# RNG_SATA.net
KiCad netlist of a schematic drawn in Altium Designer
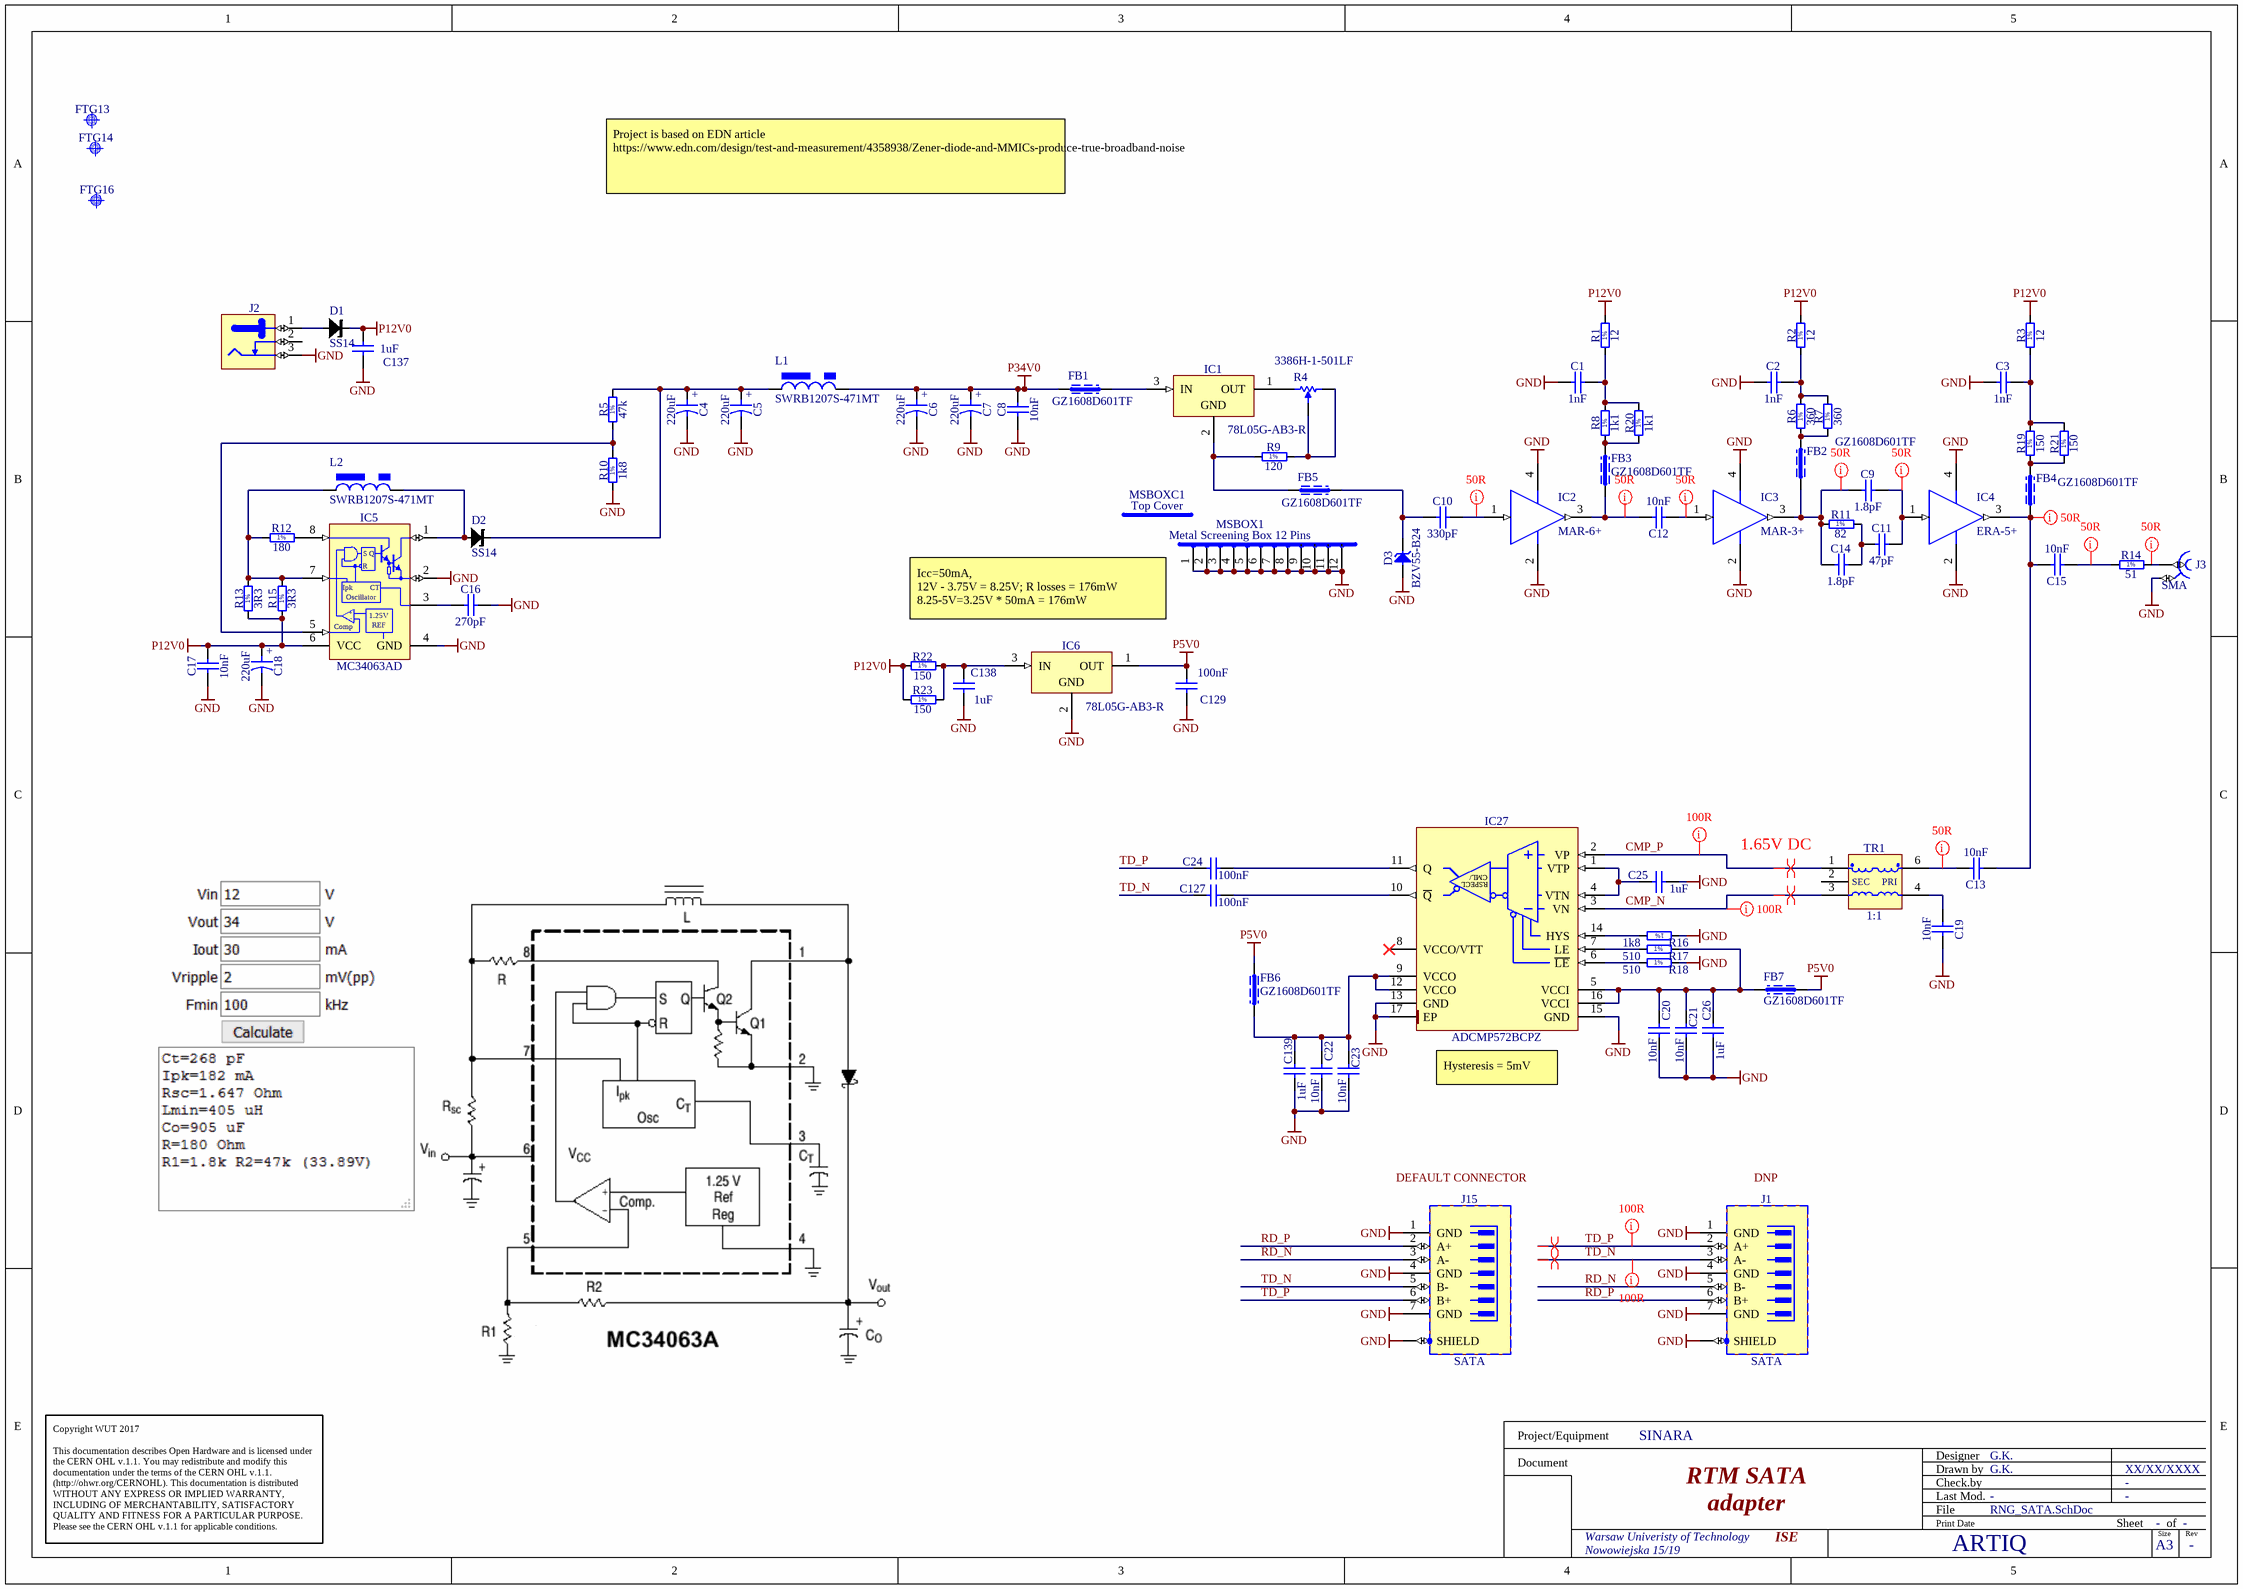
[diagram p0: RNG_SATA.SchDoc]

(export (version "E")
  (design (tool "Eeschema 10.0.6"))
  (components
    (comp (ref "C1")
      (value "1nF")
      (footprint "CAPC1608X90N")
      (description "Non-polarised capacitor")
      (fields
        (field (name "PART NUMBER") "CC0603_1NF_50V_1%_NP0")
        (field (name "VOLTAGE") "50V")
        (field (name "AUTHOR") "CERN DEM JLC")
      )
      (libsource (lib "Capacitors") (part "Capacitor - non polarized"))
    )
    (comp (ref "C2")
      (value "1nF")
      (footprint "CAPC1608X90N")
      (description "Non-polarised capacitor")
      (fields
        (field (name "PART NUMBER") "CC0603_1NF_50V_1%_NP0")
        (field (name "VOLTAGE") "50V")
        (field (name "AUTHOR") "CERN DEM JLC")
      )
      (libsource (lib "Capacitors") (part "Capacitor - non polarized"))
    )
    (comp (ref "C3")
      (value "1nF")
      (footprint "CAPC1608X90N")
      (description "Non-polarised capacitor")
      (fields
        (field (name "PART NUMBER") "CC0603_1NF_50V_1%_NP0")
        (field (name "VOLTAGE") "50V")
        (field (name "AUTHOR") "CERN DEM JLC")
      )
      (libsource (lib "Capacitors") (part "Capacitor - non polarized"))
    )
    (comp (ref "C4")
      (value "220uF")
      (footprint "CAPAE830X1020N")
      (description "Polarised capacitor")
      (fields
        (field (name "PART NUMBER") "CAE830-1020_220UF_35V_20%")
        (field (name "VOLTAGE") "35V")
        (field (name "AUTHOR") "CERN DEM JLC")
      )
      (libsource (lib "Capacitors") (part "Capacitor - polarized"))
    )
    (comp (ref "C5")
      (value "220uF")
      (footprint "CAPAE830X1020N")
      (description "Polarised capacitor")
      (fields
        (field (name "PART NUMBER") "CAE830-1020_220UF_35V_20%")
        (field (name "VOLTAGE") "35V")
        (field (name "AUTHOR") "CERN DEM JLC")
      )
      (libsource (lib "Capacitors") (part "Capacitor - polarized"))
    )
    (comp (ref "C6")
      (value "220uF")
      (footprint "CAPAE830X1020N")
      (description "Polarised capacitor")
      (fields
        (field (name "PART NUMBER") "CAE830-1020_220UF_35V_20%")
        (field (name "VOLTAGE") "35V")
        (field (name "AUTHOR") "CERN DEM JLC")
      )
      (libsource (lib "Capacitors") (part "Capacitor - polarized"))
    )
    (comp (ref "C7")
      (value "220uF")
      (footprint "CAPAE830X1020N")
      (description "Polarised capacitor")
      (fields
        (field (name "PART NUMBER") "CAE830-1020_220UF_35V_20%")
        (field (name "VOLTAGE") "35V")
        (field (name "AUTHOR") "CERN DEM JLC")
      )
      (libsource (lib "Capacitors") (part "Capacitor - polarized"))
    )
    (comp (ref "C8")
      (value "10nF")
      (footprint "CAPC1608X87N")
      (description "Non-polarised capacitor")
      (fields
        (field (name "PART NUMBER") "CC0603_10NF_50V_5%_C0G")
        (field (name "VOLTAGE") "50V")
        (field (name "AUTHOR") "CERN DEM JLC")
      )
      (libsource (lib "Capacitors") (part "Capacitor - non polarized"))
    )
    (comp (ref "C9")
      (value "1.8pF")
      (footprint "CAPC1608X87N")
      (description "Non-polarised capacitor")
      (fields
        (field (name "PART NUMBER") "CC0603_1.8PF_50V_0.25PF_NP0")
        (field (name "VOLTAGE") "50V")
        (field (name "AUTHOR") "CERN DEM JLC")
      )
      (libsource (lib "Capacitors") (part "Capacitor - non polarized"))
    )
    (comp (ref "C10")
      (value "330pF")
      (footprint "CAPC1608X87N")
      (description "Non-polarised capacitor")
      (fields
        (field (name "PART NUMBER") "CC0603_330PF_50V_5%_NP0")
        (field (name "VOLTAGE") "50V")
        (field (name "AUTHOR") "CERN DEM JLC")
      )
      (libsource (lib "Capacitors") (part "Capacitor - non polarized"))
    )
    (comp (ref "C11")
      (value "47pF")
      (footprint "CAPC1608X87N")
      (description "Non-polarised capacitor")
      (fields
        (field (name "PART NUMBER") "CC0603_47PF_50V_5%_NP0")
        (field (name "VOLTAGE") "50V")
        (field (name "AUTHOR") "CERN DEM JLC")
      )
      (libsource (lib "Capacitors") (part "Capacitor - non polarized"))
    )
    (comp (ref "C12")
      (value "10nF")
      (footprint "CAPC1608X87N")
      (description "Non-polarised capacitor")
      (fields
        (field (name "PART NUMBER") "CC0603_10NF_50V_5%_C0G")
        (field (name "VOLTAGE") "50V")
        (field (name "AUTHOR") "CERN DEM JLC")
      )
      (libsource (lib "Capacitors") (part "Capacitor - non polarized"))
    )
    (comp (ref "C13")
      (value "10nF")
      (footprint "CAPC1608X87N")
      (description "Non-polarised capacitor")
      (fields
        (field (name "PART NUMBER") "CC0603_10NF_50V_5%_C0G")
        (field (name "VOLTAGE") "50V")
        (field (name "AUTHOR") "CERN DEM JLC")
      )
      (libsource (lib "Capacitors") (part "Capacitor - non polarized"))
    )
    (comp (ref "C14")
      (value "1.8pF")
      (footprint "CAPC1608X87N")
      (description "Non-polarised capacitor")
      (fields
        (field (name "PART NUMBER") "CC0603_1.8PF_50V_0.25PF_NP0")
        (field (name "VOLTAGE") "50V")
        (field (name "AUTHOR") "CERN DEM JLC")
      )
      (libsource (lib "Capacitors") (part "Capacitor - non polarized"))
    )
    (comp (ref "C15")
      (value "10nF")
      (footprint "CAPC1608X87N")
      (description "Non-polarised capacitor")
      (fields
        (field (name "PART NUMBER") "CC0603_10NF_50V_5%_C0G")
        (field (name "VOLTAGE") "50V")
        (field (name "AUTHOR") "CERN DEM JLC")
      )
      (libsource (lib "Capacitors") (part "Capacitor - non polarized"))
    )
    (comp (ref "C16")
      (value "270pF")
      (footprint "CAPC1608X87N")
      (description "Non-polarised capacitor")
      (fields
        (field (name "PART NUMBER") "CC0603_270PF_50V_5%_NP0")
        (field (name "VOLTAGE") "50V")
        (field (name "AUTHOR") "CERN DEM JLC")
      )
      (libsource (lib "Capacitors") (part "Capacitor - non polarized"))
    )
    (comp (ref "C17")
      (value "10nF")
      (footprint "CAPC1608X87N")
      (description "Non-polarised capacitor")
      (fields
        (field (name "PART NUMBER") "CC0603_10NF_50V_5%_C0G")
        (field (name "VOLTAGE") "50V")
        (field (name "AUTHOR") "CERN DEM JLC")
      )
      (libsource (lib "Capacitors") (part "Capacitor - non polarized"))
    )
    (comp (ref "C18")
      (value "220uF")
      (footprint "CAPAE830X1020N")
      (description "Polarised capacitor")
      (fields
        (field (name "PART NUMBER") "CAE830-1020_220UF_35V_20%")
        (field (name "VOLTAGE") "35V")
        (field (name "AUTHOR") "CERN DEM JLC")
      )
      (libsource (lib "Capacitors") (part "Capacitor - polarized"))
    )
    (comp (ref "C19")
      (value "10nF")
      (footprint "CAPC1608X87N")
      (description "Non-polarised capacitor")
      (fields
        (field (name "PART NUMBER") "CC0603_10NF_50V_5%_C0G")
        (field (name "VOLTAGE") "50V")
        (field (name "AUTHOR") "CERN DEM JLC")
      )
      (libsource (lib "Capacitors") (part "Capacitor - non polarized"))
    )
    (comp (ref "C20")
      (value "10nF")
      (footprint "CAPC1608X87N")
      (description "Non-polarised capacitor")
      (fields
        (field (name "PART NUMBER") "CC0603_10NF_50V_5%_C0G")
        (field (name "VOLTAGE") "50V")
        (field (name "AUTHOR") "CERN DEM JLC")
      )
      (libsource (lib "Capacitors") (part "Capacitor - non polarized"))
    )
    (comp (ref "C21")
      (value "10nF")
      (footprint "CAPC1608X87N")
      (description "Non-polarised capacitor")
      (fields
        (field (name "PART NUMBER") "CC0603_10NF_50V_5%_C0G")
        (field (name "VOLTAGE") "50V")
        (field (name "AUTHOR") "CERN DEM JLC")
      )
      (libsource (lib "Capacitors") (part "Capacitor - non polarized"))
    )
    (comp (ref "C22")
      (value "10nF")
      (footprint "CAPC1608X87N")
      (description "Non-polarised capacitor")
      (fields
        (field (name "PART NUMBER") "CC0603_10NF_50V_5%_C0G")
        (field (name "VOLTAGE") "50V")
        (field (name "AUTHOR") "CERN DEM JLC")
      )
      (libsource (lib "Capacitors") (part "Capacitor - non polarized"))
    )
    (comp (ref "C23")
      (value "10nF")
      (footprint "CAPC1608X87N")
      (description "Non-polarised capacitor")
      (fields
        (field (name "PART NUMBER") "CC0603_10NF_50V_5%_C0G")
        (field (name "VOLTAGE") "50V")
        (field (name "AUTHOR") "CERN DEM JLC")
      )
      (libsource (lib "Capacitors") (part "Capacitor - non polarized"))
    )
    (comp (ref "C24")
      (value "100nF")
      (footprint "CAPC1005X55N")
      (description "Non-polarised capacitor")
      (fields
        (field (name "PART NUMBER") "CC0402_100NF_16V_10%_X7R")
        (field (name "VOLTAGE") "16V")
        (field (name "AUTHOR") "CERN DEM JLC")
      )
      (libsource (lib "Capacitors") (part "Capacitor - non polarized"))
    )
    (comp (ref "C25")
      (value "1uF")
      (footprint "CAPC1608X87N")
      (description "Non-polarised capacitor")
      (fields
        (field (name "PART NUMBER") "CC0603_1UF_16V_10%_X7R")
        (field (name "VOLTAGE") "16V")
        (field (name "AUTHOR") "CERN DEM JLC")
      )
      (libsource (lib "Capacitors") (part "Capacitor - non polarized"))
    )
    (comp (ref "C26")
      (value "1uF")
      (footprint "CAPC1608X87N")
      (description "Non-polarised capacitor")
      (fields
        (field (name "PART NUMBER") "CC0603_1UF_16V_10%_X7R")
        (field (name "VOLTAGE") "16V")
        (field (name "AUTHOR") "CERN DEM JLC")
      )
      (libsource (lib "Capacitors") (part "Capacitor - non polarized"))
    )
    (comp (ref "C127")
      (value "100nF")
      (footprint "CAPC1005X55N")
      (description "Non-polarised capacitor")
      (fields
        (field (name "PART NUMBER") "CC0402_100NF_16V_10%_X7R")
        (field (name "VOLTAGE") "16V")
        (field (name "AUTHOR") "CERN DEM JLC")
      )
      (libsource (lib "Capacitors") (part "Capacitor - non polarized"))
    )
    (comp (ref "C129")
      (value "100nF")
      (footprint "CAPC1005X55N")
      (description "Non-polarised capacitor")
      (fields
        (field (name "PART NUMBER") "CC0402_100NF_16V_10%_X7R")
        (field (name "VOLTAGE") "16V")
        (field (name "AUTHOR") "CERN DEM JLC")
      )
      (libsource (lib "Capacitors") (part "Capacitor - non polarized"))
    )
    (comp (ref "C137")
      (value "1uF")
      (footprint "CAPC1608X87N")
      (description "Non-polarised capacitor")
      (fields
        (field (name "PART NUMBER") "CC0603_1UF_16V_10%_X7R")
        (field (name "VOLTAGE") "16V")
        (field (name "AUTHOR") "CERN DEM JLC")
      )
      (libsource (lib "Capacitors") (part "Capacitor - non polarized"))
    )
    (comp (ref "C138")
      (value "1uF")
      (footprint "CAPC1608X87N")
      (description "Non-polarised capacitor")
      (fields
        (field (name "PART NUMBER") "CC0603_1UF_16V_10%_X7R")
        (field (name "VOLTAGE") "16V")
        (field (name "AUTHOR") "CERN DEM JLC")
      )
      (libsource (lib "Capacitors") (part "Capacitor - non polarized"))
    )
    (comp (ref "C139")
      (value "1uF")
      (footprint "CAPC1608X87N")
      (description "Non-polarised capacitor")
      (fields
        (field (name "PART NUMBER") "CC0603_1UF_16V_10%_X7R")
        (field (name "VOLTAGE") "16V")
        (field (name "AUTHOR") "CERN DEM JLC")
      )
      (libsource (lib "Capacitors") (part "Capacitor - non polarized"))
    )
    (comp (ref "D1")
      (value "SS14")
      (footprint "DO-214AC/SMA")
      (description "1A 80V shottky diode (Maritex)")
      (libsource (lib "Diodes") (part "D_SS14"))
    )
    (comp (ref "D2")
      (value "SS14")
      (footprint "DO-214AC/SMA")
      (description "1A 80V shottky diode (Maritex)")
      (libsource (lib "Diodes") (part "D_SS14"))
    )
    (comp (ref "D3")
      (value "BZV55-B24")
      (footprint "DIOMELF3515N")
      (description "Zener Diode")
      (fields
        (field (name "VOLTAGE") "24V")
        (field (name "POWER") "500mW")
        (field (name "AUTHOR") "CERN DEM JLC")
      )
      (libsource (lib "ICs And Semiconductors") (part "Diode Zener"))
    )
    (comp (ref "FB1")
      (value "GZ1608D601TF")
      (footprint "0603L")
      (description "ferrite bead 100R@100MHz 1A")
      (libsource (lib "Inductors_Transformers") (part "L_FERRITE_BEAD_0603"))
    )
    (comp (ref "FB2")
      (value "GZ1608D601TF")
      (footprint "0603L")
      (description "ferrite bead 100R@100MHz 1A")
      (libsource (lib "Inductors_Transformers") (part "L_FERRITE_BEAD_0603"))
    )
    (comp (ref "FB3")
      (value "GZ1608D601TF")
      (footprint "0603L")
      (description "ferrite bead 100R@100MHz 1A")
      (libsource (lib "Inductors_Transformers") (part "L_FERRITE_BEAD_0603"))
    )
    (comp (ref "FB4")
      (value "GZ1608D601TF")
      (footprint "0603L")
      (description "ferrite bead 100R@100MHz 1A")
      (libsource (lib "Inductors_Transformers") (part "L_FERRITE_BEAD_0603"))
    )
    (comp (ref "FB5")
      (value "GZ1608D601TF")
      (footprint "0603L")
      (description "ferrite bead 100R@100MHz 1A")
      (libsource (lib "Inductors_Transformers") (part "L_FERRITE_BEAD_0603"))
    )
    (comp (ref "FB6")
      (value "GZ1608D601TF")
      (footprint "0603L")
      (description "ferrite bead 100R@100MHz 1A")
      (libsource (lib "Inductors_Transformers") (part "L_FERRITE_BEAD_0603"))
    )
    (comp (ref "FB7")
      (value "GZ1608D601TF")
      (footprint "0603L")
      (description "ferrite bead 100R@100MHz 1A")
      (libsource (lib "Inductors_Transformers") (part "L_FERRITE_BEAD_0603"))
    )
    (comp (ref "FTG13")
      (value "Use only in PCB")
      (footprint "FIDUCIAL_TOP_C100-200")
      (description "Fiducial Target")
      (fields (field (name "PART NUMBER") "FIDUCIAL_TARGET_C100-200") (field (name "AUTHOR") "CERN DEM JLC"))
      (libsource (lib "Eletro-mechanical") (part "Fiducial Target"))
    )
    (comp (ref "FTG14")
      (value "Use only in PCB")
      (footprint "FIDUCIAL_TOP_S100-200")
      (description "Fiducial Target")
      (fields (field (name "PART NUMBER") "FIDUCIAL_TARGET_S100-200") (field (name "AUTHOR") "CERN DEM JLC"))
      (libsource (lib "Eletro-mechanical") (part "Fiducial Target"))
    )
    (comp (ref "FTG16")
      (value "Use only in PCB")
      (footprint "FIDUCIAL_TOP_S100-200")
      (description "Fiducial Target")
      (fields (field (name "PART NUMBER") "FIDUCIAL_TARGET_S100-200") (field (name "AUTHOR") "CERN DEM JLC"))
      (libsource (lib "Eletro-mechanical") (part "Fiducial Target"))
    )
    (comp (ref "IC1")
      (value "78L05G-AB3-R")
      (footprint "SOT89")
      (description "3-Terminal Regulator 1=OUT 2=GND 3=IN")
      (fields
        (field (name "PART NUMBER") "L78L05ACUTR")
        (field (name "MANUFACTURER") "ST MICROELECTRONICS")
        (field (name "AUTHOR") "CERN DEM JLC")
      )
      (libsource (lib "ICs And Semiconductors") (part "REG3 1OUT-2GND-3IN"))
    )
    (comp (ref "IC2")
      (value "MAR-6+")
      (footprint "MINI-CIRCUITS_VV105")
      (description "Monolithic Amplifier DC-2GHz")
      (fields (field (name "MANUFACTURER") "MINI-CIRCUITS") (field (name "AUTHOR") "CERN DEM MR"))
      (libsource (lib "ICs_Analog_Interfaces") (part "RF_MAR-6+"))
    )
    (comp (ref "IC3")
      (value "MAR-3+")
      (footprint "MINI-CIRCUITS_VV105")
      (description "Monolithic Amplifier DC-2GHz")
      (fields (field (name "MANUFACTURER") "MINI-CIRCUITS") (field (name "AUTHOR") "CERN DEM MR"))
      (libsource (lib "ICs_Analog_Interfaces") (part "RF_MAR-3+"))
    )
    (comp (ref "IC4")
      (value "ERA-5+")
      (footprint "MINI-CIRCUITS_VV105")
      (description "Monolithic Amplifier DC-4GHz")
      (fields (field (name "MANUFACTURER") "MINI-CIRCUITS") (field (name "AUTHOR") "CERN DEM MR"))
      (libsource (lib "ICs_Analog_Interfaces") (part "RF_ERA-5+"))
    )
    (comp (ref "IC5")
      (value "MC34063AD")
      (footprint "SOIC127P600X175-8N")
      (description "3V to 40V 1.5A Peak Boost/Buck/Inverting Switching Regulator")
      (fields (field (name "MANUFACTURER") "TEXAS INSTRUMENTS") (field (name "AUTHOR") "CERN DEM JLC"))
      (libsource (lib "ICs And Semiconductors") (part "MC34063A"))
    )
    (comp (ref "IC6")
      (value "78L05G-AB3-R")
      (footprint "SOT89")
      (description "3-Terminal Regulator 1=OUT 2=GND 3=IN")
      (fields
        (field (name "PART NUMBER") "L78L05ACUTR")
        (field (name "MANUFACTURER") "ST MICROELECTRONICS")
        (field (name "AUTHOR") "CERN DEM JLC")
      )
      (libsource (lib "ICs And Semiconductors") (part "REG3 1OUT-2GND-3IN"))
    )
    (comp (ref "IC27")
      (value "ADCMP572BCPZ")
      (footprint "QFN50P300X300X100-17N-S145")
      (description "Ultrafast 3.3V/5V Single-Supply SiGe Comparator")
      (fields (field (name "MANUFACTURER") "ANALOG DEVICES") (field (name "AUTHOR") "CERN DEM JLC"))
      (libsource (lib "ICs And Semiconductors") (part "ADCMP573BCPZ"))
    )
    (comp (ref "J1")
      (value "SATA")
      (footprint "3M_5607-4200-SH")
      (description "7 Pin + 1 Shield SATA Receptacle")
      (fields
        (field (name "PART NUMBER") "3M_5607-4200-SH")
        (field (name "MANUFACTURER") "3M")
        (field (name "AUTHOR") "CERN DEM JLC")
      )
      (libsource (lib "Connectors") (part "Connector SATA 7 Male + 1 Shield"))
    )
    (comp (ref "J2")
      (value "Jack")
      (footprint "CLIFF_FC68148(DC-10A)")
      (description "12V /  5A, 2.1mm Diameter Pin, DC Power Socket With  Switch. DC10A Type")
      (fields
        (field (name "PART NUMBER") "CLIFF_FC68148(DC-10A)")
        (field (name "MANUFACTURER") "CLIFF ELECTRONIC COMPONENTS")
        (field (name "AUTHOR") "CERN DEM JLC")
      )
      (libsource (lib "Connectors") (part "CLIFF_FC68148(DC-10A)"))
    )
    (comp (ref "J3")
      (value "SMA")
      (footprint "RF249BT0050GHDW")
      (description "50 Ohm Through Hole SMA Right Angle PCB Jack")
      (fields
        (field (name "PART NUMBER") "AdamTech_RF249BT0050GHDW")
        (field (name "MANUFACTURER") "AdamTech")
        (field (name "AUTHOR") "GK")
      )
      (libsource (lib "Connectors") (part "CON_SMA_RF249BT0050GHDW"))
    )
    (comp (ref "J15")
      (value "SATA")
      (footprint "3M_5607-4200-SH")
      (description "7 Pin + 1 Shield SATA Receptacle")
      (fields
        (field (name "PART NUMBER") "3M_5607-4200-SH")
        (field (name "MANUFACTURER") "3M")
        (field (name "AUTHOR") "CERN DEM JLC")
      )
      (libsource (lib "Connectors") (part "Connector SATA 7 Male + 1 Shield"))
    )
    (comp (ref "L1")
      (value "SWRB1207S-471MT")
      (footprint "choke_DLCSS124")
      (description "inductor")
      (libsource (lib "Inductors_Transformers") (part "L_POWER_CSS124"))
    )
    (comp (ref "L2")
      (value "SWRB1207S-471MT")
      (footprint "choke_DLCSS124")
      (description "inductor")
      (libsource (lib "Inductors_Transformers") (part "L_POWER_CSS124"))
    )
    (comp (ref "MSBOX1")
      (value "Metal Screening Box 12 Pins")
      (footprint "MSBOX_TE_2118728-2")
      (fields
        (field (name "PART NUMBER") "MSBOX_TE_2118728-2")
        (field (name "MANUFACTURER") "Tyco Electronics")
        (field (name "MANUFACTURER PART NUMBER") "BMI-S-202-F")
        (field (name "AUTHOR") "GK")
      )
      (libsource (lib "Mechanical") (part "SH_TE_2118728-2"))
    )
    (comp (ref "MSBOXC1")
      (value "Top Cover")
      (footprint "MSBOX_TE_2118727-2")
      (description "Metal Screening Box - Top Cover 0 Pin")
      (fields
        (field (name "PART NUMBER") "MSBOX_TE_2118727-2")
        (field (name "MANUFACTURER") "Tyco Electronics")
        (field (name "AUTHOR") "GK")
      )
      (libsource (lib "Mechanical") (part "SH_TE_2118727-2"))
    )
    (comp (ref "R1")
      (value "12")
      (footprint "RESC1608X55N")
      (description "Resistor - 1%")
      (fields
        (field (name "PART NUMBER") "R0603_12R_1%_0.1W_100PPM")
        (field (name "POWER") "0.1W")
        (field (name "AUTHOR") "CERN DEM JLC")
      )
      (libsource (lib "Resistors") (part "Resistor - 1%"))
    )
    (comp (ref "R2")
      (value "12")
      (footprint "RESC1608X55N")
      (description "Resistor - 1%")
      (fields
        (field (name "PART NUMBER") "R0603_12R_1%_0.1W_100PPM")
        (field (name "POWER") "0.1W")
        (field (name "AUTHOR") "CERN DEM JLC")
      )
      (libsource (lib "Resistors") (part "Resistor - 1%"))
    )
    (comp (ref "R3")
      (value "12")
      (footprint "RESC1608X55N")
      (description "Resistor - 1%")
      (fields
        (field (name "PART NUMBER") "R0603_12R_1%_0.1W_100PPM")
        (field (name "POWER") "0.1W")
        (field (name "AUTHOR") "CERN DEM JLC")
      )
      (libsource (lib "Resistors") (part "Resistor - 1%"))
    )
    (comp (ref "R4")
      (value "3386H-1-501LF")
      (footprint "BOUR-3386H")
      (fields (field (name "TOLERANCE") "10%") (field (name "MANUFACTURER") "Bourns"))
      (libsource (lib "Altium Content Vault") (part "RES-ADJ-3_A"))
    )
    (comp (ref "R5")
      (value "47k")
      (footprint "RESC1608X55N")
      (description "Resistor - 1%")
      (fields
        (field (name "PART NUMBER") "R0603_47K_1%_0.1W_100PPM")
        (field (name "POWER") "0.1W")
        (field (name "AUTHOR") "CERN DEM JLC")
      )
      (libsource (lib "Resistors") (part "Resistor - 1%"))
    )
    (comp (ref "R6")
      (value "360")
      (footprint "RESC2012X60N")
      (description "Resistor - 1%")
      (fields
        (field (name "PART NUMBER") "R0805_360R_1%_0.125W_100PPM")
        (field (name "POWER") "0.125W")
        (field (name "AUTHOR") "CERN DEM JLC")
      )
      (libsource (lib "Resistors") (part "Resistor - 1%"))
    )
    (comp (ref "R7")
      (value "360")
      (footprint "RESC2012X60N")
      (description "Resistor - 1%")
      (fields
        (field (name "PART NUMBER") "R0805_360R_1%_0.125W_100PPM")
        (field (name "POWER") "0.125W")
        (field (name "AUTHOR") "CERN DEM JLC")
      )
      (libsource (lib "Resistors") (part "Resistor - 1%"))
    )
    (comp (ref "R8")
      (value "1k1")
      (footprint "RESC1608X55N")
      (description "Resistor - 1%")
      (fields
        (field (name "PART NUMBER") "R0603_1K1_1%_0.1W_100PPM")
        (field (name "POWER") "0.1W")
        (field (name "AUTHOR") "CERN DEM JLC")
      )
      (libsource (lib "Resistors") (part "Resistor - 1%"))
    )
    (comp (ref "R9")
      (value "120")
      (footprint "RESC1608X55N")
      (description "Resistor - 1%")
      (fields
        (field (name "PART NUMBER") "R0603_120R_1%_0.1W_100PPM")
        (field (name "POWER") "0.1W")
        (field (name "AUTHOR") "CERN DEM JLC")
      )
      (libsource (lib "Resistors") (part "Resistor - 1%"))
    )
    (comp (ref "R10")
      (value "1k8")
      (footprint "RESC1608X55N")
      (description "Resistor - 1%")
      (fields
        (field (name "PART NUMBER") "R0603_1K8_1%_0.1W_100PPM")
        (field (name "POWER") "0.1W")
        (field (name "AUTHOR") "CERN DEM JLC")
      )
      (libsource (lib "Resistors") (part "Resistor - 1%"))
    )
    (comp (ref "R11")
      (value "82")
      (footprint "RESC1608X55N")
      (description "Resistor - 1%")
      (fields
        (field (name "PART NUMBER") "R0603_82R_1%_0.1W_100PPM")
        (field (name "POWER") "0.1W")
        (field (name "AUTHOR") "CERN DEM JLC")
      )
      (libsource (lib "Resistors") (part "Resistor - 1%"))
    )
    (comp (ref "R12")
      (value "180")
      (footprint "RESC1608X55N")
      (description "Resistor - 1%")
      (fields
        (field (name "PART NUMBER") "R0603_180R_1%_0.1W_100PPM")
        (field (name "POWER") "0.1W")
        (field (name "AUTHOR") "CERN DEM JLC")
      )
      (libsource (lib "Resistors") (part "Resistor - 1%"))
    )
    (comp (ref "R13")
      (value "3R3")
      (footprint "RESC2012X60N")
      (description "Resistor - 1%")
      (fields
        (field (name "PART NUMBER") "R0805_3R3_1%_0.125W_200PPM")
        (field (name "POWER") "0.125W")
        (field (name "AUTHOR") "CERN DEM JLC")
      )
      (libsource (lib "Resistors") (part "Resistor - 1%"))
    )
    (comp (ref "R14")
      (value "51")
      (footprint "RESC1608X55N")
      (description "Resistor - 1%")
      (fields
        (field (name "PART NUMBER") "R0603_51R_1%_0.1W_100PPM")
        (field (name "POWER") "0.1W")
        (field (name "AUTHOR") "CERN DEM JLC")
      )
      (libsource (lib "Resistors") (part "Resistor - 1%"))
    )
    (comp (ref "R15")
      (value "3R3")
      (footprint "RESC2012X60N")
      (description "Resistor - 1%")
      (fields
        (field (name "PART NUMBER") "R0805_3R3_1%_0.125W_200PPM")
        (field (name "POWER") "0.125W")
        (field (name "AUTHOR") "CERN DEM JLC")
      )
      (libsource (lib "Resistors") (part "Resistor - 1%"))
    )
    (comp (ref "R16")
      (value "1k8")
      (footprint "RESC1608X55N")
      (description "Resistor - 1%")
      (fields
        (field (name "PART NUMBER") "R0603_1K8_1%_0.1W_100PPM")
        (field (name "POWER") "0.1W")
        (field (name "AUTHOR") "CERN DEM JLC")
      )
      (libsource (lib "Resistors") (part "Resistor - 1%"))
    )
    (comp (ref "R17")
      (value "510")
      (footprint "RESC1608X55N")
      (description "Resistor - 1%")
      (fields
        (field (name "PART NUMBER") "R0603_510R_1%_0.1W_100PPM")
        (field (name "POWER") "0.1W")
        (field (name "AUTHOR") "CERN DEM JLC")
      )
      (libsource (lib "Resistors") (part "Resistor - 1%"))
    )
    (comp (ref "R18")
      (value "510")
      (footprint "RESC1608X55N")
      (description "Resistor - 1%")
      (fields
        (field (name "PART NUMBER") "R0603_510R_1%_0.1W_100PPM")
        (field (name "POWER") "0.1W")
        (field (name "AUTHOR") "CERN DEM JLC")
      )
      (libsource (lib "Resistors") (part "Resistor - 1%"))
    )
    (comp (ref "R19")
      (value "150")
      (footprint "RESC2012X60N")
      (description "Resistor - 1%")
      (fields
        (field (name "PART NUMBER") "R0805_150R_1%_0.125W_100PPM")
        (field (name "POWER") "0.125W")
        (field (name "AUTHOR") "CERN DEM JLC")
      )
      (libsource (lib "Resistors") (part "Resistor - 1%"))
    )
    (comp (ref "R20")
      (value "1k1")
      (footprint "RESC1608X55N")
      (description "Resistor - 1%")
      (fields
        (field (name "PART NUMBER") "R0603_1K1_1%_0.1W_100PPM")
        (field (name "POWER") "0.1W")
        (field (name "AUTHOR") "CERN DEM JLC")
      )
      (libsource (lib "Resistors") (part "Resistor - 1%"))
    )
    (comp (ref "R21")
      (value "150")
      (footprint "RESC2012X60N")
      (description "Resistor - 1%")
      (fields
        (field (name "PART NUMBER") "R0805_150R_1%_0.125W_100PPM")
        (field (name "POWER") "0.125W")
        (field (name "AUTHOR") "CERN DEM JLC")
      )
      (libsource (lib "Resistors") (part "Resistor - 1%"))
    )
    (comp (ref "R22")
      (value "150")
      (footprint "RESC2012X60N")
      (description "Resistor - 1%")
      (fields
        (field (name "PART NUMBER") "R0805_150R_1%_0.125W_100PPM")
        (field (name "POWER") "0.125W")
        (field (name "AUTHOR") "CERN DEM JLC")
      )
      (libsource (lib "Resistors") (part "Resistor - 1%"))
    )
    (comp (ref "R23")
      (value "150")
      (footprint "RESC2012X60N")
      (description "Resistor - 1%")
      (fields
        (field (name "PART NUMBER") "R0805_150R_1%_0.125W_100PPM")
        (field (name "POWER") "0.125W")
        (field (name "AUTHOR") "CERN DEM JLC")
      )
      (libsource (lib "Resistors") (part "Resistor - 1%"))
    )
    (comp (ref "TR1")
      (value "1:1")
      (footprint "XFMR_MINI-CIRCUITS_AT224")
      (description "50 Ohms 4.5 To 3000MHz RF Transformers")
      (fields
        (field (name "PART NUMBER") "XFMR_MINI-CIRCUITS_TC1-1-13M+")
        (field (name "MANUFACTURER") "MINI-CIRCUITS")
        (field (name "AUTHOR") "CERN DEM JLC")
      )
      (libsource (lib "Inductors & Transformers") (part "XFMR_MINI-CIRCUITS_TC1-1-13M+"))
    )
  )
  (nets
    (net (code "1") (name "/CMP_N") (class "Default")
      (node (ref "IC27") (pin "3") (pinfunction "VN_3") (pintype "input"))
      (node (ref "TR1") (pin "3") (pinfunction "S_3") (pintype "passive"))
    )
    (net (code "2") (name "/CMP_P") (class "Default")
      (node (ref "IC27") (pin "2") (pinfunction "VP_2") (pintype "input"))
      (node (ref "TR1") (pin "1") (pinfunction "SDOT_1") (pintype "passive"))
    )
    (net (code "5") (name "/RD_N") (class "Default")
      (node (ref "J1") (pin "5") (pinfunction "B-_5") (pintype "bidirectional"))
      (node (ref "J15") (pin "3") (pinfunction "A-_3") (pintype "bidirectional"))
    )
    (net (code "6") (name "/RD_P") (class "Default")
      (node (ref "J1") (pin "6") (pinfunction "B+_6") (pintype "bidirectional"))
      (node (ref "J15") (pin "2") (pinfunction "A+_2") (pintype "bidirectional"))
    )
    (net (code "7") (name "/TD_N") (class "Default")
      (node (ref "C127") (pin "1") (pinfunction "1_1") (pintype "passive"))
      (node (ref "J1") (pin "3") (pinfunction "A-_3") (pintype "bidirectional"))
      (node (ref "J15") (pin "5") (pinfunction "B-_5") (pintype "bidirectional"))
    )
    (net (code "8") (name "/TD_P") (class "Default")
      (node (ref "C24") (pin "2") (pinfunction "2_2") (pintype "passive"))
      (node (ref "J1") (pin "2") (pinfunction "A+_2") (pintype "bidirectional"))
      (node (ref "J15") (pin "6") (pinfunction "B+_6") (pintype "bidirectional"))
    )
    (net (code "9") (name "GND") (class "Default")
      (node (ref "C1") (pin "1") (pinfunction "1_1") (pintype "passive"))
      (node (ref "C129") (pin "2") (pinfunction "2_2") (pintype "passive"))
      (node (ref "C137") (pin "1") (pinfunction "1_1") (pintype "passive"))
      (node (ref "C138") (pin "1") (pinfunction "1_1") (pintype "passive"))
      (node (ref "C139") (pin "1") (pinfunction "1_1") (pintype "passive"))
      (node (ref "C16") (pin "2") (pinfunction "2_2") (pintype "passive"))
      (node (ref "C17") (pin "1") (pinfunction "1_1") (pintype "passive"))
      (node (ref "C18") (pin "2") (pinfunction "2_2") (pintype "passive"))
      (node (ref "C19") (pin "2") (pinfunction "2_2") (pintype "passive"))
      (node (ref "C2") (pin "1") (pinfunction "1_1") (pintype "passive"))
      (node (ref "C20") (pin "2") (pinfunction "2_2") (pintype "passive"))
      (node (ref "C21") (pin "2") (pinfunction "2_2") (pintype "passive"))
      (node (ref "C22") (pin "2") (pinfunction "2_2") (pintype "passive"))
      (node (ref "C23") (pin "2") (pinfunction "2_2") (pintype "passive"))
      (node (ref "C25") (pin "2") (pinfunction "2_2") (pintype "passive"))
      (node (ref "C26") (pin "1") (pinfunction "1_1") (pintype "passive"))
      (node (ref "C3") (pin "1") (pinfunction "1_1") (pintype "passive"))
      (node (ref "C4") (pin "2") (pinfunction "2_2") (pintype "passive"))
      (node (ref "C5") (pin "2") (pinfunction "2_2") (pintype "passive"))
      (node (ref "C6") (pin "2") (pinfunction "2_2") (pintype "passive"))
      (node (ref "C7") (pin "2") (pinfunction "2_2") (pintype "passive"))
      (node (ref "C8") (pin "1") (pinfunction "1_1") (pintype "passive"))
      (node (ref "D3") (pin "2") (pinfunction "A_2") (pintype "passive"))
      (node (ref "IC2") (pin "2") (pinfunction "GND_2") (pintype "power_in"))
      (node (ref "IC2") (pin "4") (pinfunction "GND_4") (pintype "power_in"))
      (node (ref "IC27") (pin "13") (pinfunction "GND_13") (pintype "power_in"))
      (node (ref "IC27") (pin "15") (pinfunction "GND_15") (pintype "power_in"))
      (node (ref "IC27") (pin "17") (pinfunction "EP_17") (pintype "power_in"))
      (node (ref "IC3") (pin "2") (pinfunction "GND_2") (pintype "power_in"))
      (node (ref "IC3") (pin "4") (pinfunction "GND_4") (pintype "power_in"))
      (node (ref "IC4") (pin "2") (pinfunction "GND_2") (pintype "power_in"))
      (node (ref "IC4") (pin "4") (pinfunction "GND_4") (pintype "power_in"))
      (node (ref "IC5") (pin "2") (pinfunction "SWE_2") (pintype "bidirectional"))
      (node (ref "IC5") (pin "4") (pinfunction "GND_4") (pintype "power_in"))
      (node (ref "IC6") (pin "2") (pinfunction "GND_2") (pintype "power_in"))
      (node (ref "J1") (pin "1") (pinfunction "GND_1") (pintype "power_in"))
      (node (ref "J1") (pin "4") (pinfunction "GND_4") (pintype "power_in"))
      (node (ref "J1") (pin "7") (pinfunction "GND_7") (pintype "power_in"))
      (node (ref "J1") (pin "8") (pinfunction "SHIELD_8") (pintype "bidirectional"))
      (node (ref "J15") (pin "1") (pinfunction "GND_1") (pintype "power_in"))
      (node (ref "J15") (pin "4") (pinfunction "GND_4") (pintype "power_in"))
      (node (ref "J15") (pin "7") (pinfunction "GND_7") (pintype "power_in"))
      (node (ref "J15") (pin "8") (pinfunction "SHIELD_8") (pintype "bidirectional"))
      (node (ref "J2") (pin "3") (pinfunction "3_3") (pintype "bidirectional"))
      (node (ref "J3") (pin "2") (pinfunction "2_2") (pintype "bidirectional"))
      (node (ref "MSBOX1") (pin "1") (pinfunction "1_1") (pintype "passive"))
      (node (ref "MSBOX1") (pin "10") (pinfunction "10_10") (pintype "power_in"))
      (node (ref "MSBOX1") (pin "11") (pinfunction "11_11") (pintype "power_in"))
      (node (ref "MSBOX1") (pin "12") (pinfunction "12_12") (pintype "power_in"))
      (node (ref "MSBOX1") (pin "2") (pinfunction "2_2") (pintype "passive"))
      (node (ref "MSBOX1") (pin "3") (pinfunction "3_3") (pintype "passive"))
      (node (ref "MSBOX1") (pin "4") (pinfunction "4_4") (pintype "passive"))
      (node (ref "MSBOX1") (pin "5") (pinfunction "5_5") (pintype "passive"))
      (node (ref "MSBOX1") (pin "6") (pinfunction "6_6") (pintype "passive"))
      (node (ref "MSBOX1") (pin "7") (pinfunction "7_7") (pintype "passive"))
      (node (ref "MSBOX1") (pin "8") (pinfunction "8_8") (pintype "passive"))
      (node (ref "MSBOX1") (pin "9") (pinfunction "9_9") (pintype "power_in"))
      (node (ref "R10") (pin "1") (pinfunction "1_1") (pintype "passive"))
      (node (ref "R16") (pin "1") (pinfunction "1_1") (pintype "passive"))
      (node (ref "R18") (pin "2") (pinfunction "2_2") (pintype "passive"))
    )
    (net (code "10") (name "Net-(C1-Pad2)") (class "Default")
      (node (ref "C1") (pin "2") (pinfunction "2_2") (pintype "passive"))
      (node (ref "R1") (pin "1") (pinfunction "1_1") (pintype "passive"))
      (node (ref "R20") (pin "2") (pinfunction "2_2") (pintype "passive"))
      (node (ref "R8") (pin "2") (pinfunction "2_2") (pintype "passive"))
    )
    (net (code "11") (name "Net-(C2-Pad2)") (class "Default")
      (node (ref "C2") (pin "2") (pinfunction "2_2") (pintype "passive"))
      (node (ref "R2") (pin "1") (pinfunction "1_1") (pintype "passive"))
      (node (ref "R6") (pin "2") (pinfunction "2_2") (pintype "passive"))
      (node (ref "R7") (pin "2") (pinfunction "2_2") (pintype "passive"))
    )
    (net (code "12") (name "Net-(C3-Pad2)") (class "Default")
      (node (ref "C3") (pin "2") (pinfunction "2_2") (pintype "passive"))
      (node (ref "R19") (pin "2") (pinfunction "2_2") (pintype "passive"))
      (node (ref "R21") (pin "2") (pinfunction "2_2") (pintype "passive"))
      (node (ref "R3") (pin "1") (pinfunction "1_1") (pintype "passive"))
    )
    (net (code "13") (name "Net-(C4-Pad1)") (class "Default")
      (node (ref "C4") (pin "1") (pinfunction "1_1") (pintype "passive"))
      (node (ref "C5") (pin "1") (pinfunction "1_1") (pintype "passive"))
      (node (ref "D2") (pin "K") (pinfunction "K_K") (pintype "passive"))
      (node (ref "L1") (pin "1") (pintype "passive"))
      (node (ref "R5") (pin "2") (pinfunction "2_2") (pintype "passive"))
    )
    (net (code "14") (name "Net-(C11-Pad1)") (class "Default")
      (node (ref "C11") (pin "1") (pinfunction "1_1") (pintype "passive"))
      (node (ref "C14") (pin "2") (pinfunction "2_2") (pintype "passive"))
      (node (ref "R11") (pin "2") (pinfunction "2_2") (pintype "passive"))
    )
    (net (code "15") (name "Net-(C15-Pad1)") (class "Default")
      (node (ref "C15") (pin "1") (pinfunction "1_1") (pintype "passive"))
      (node (ref "R14") (pin "1") (pinfunction "1_1") (pintype "passive"))
    )
    (net (code "16") (name "Net-(C20-Pad1)") (class "Default")
      (node (ref "C20") (pin "1") (pinfunction "1_1") (pintype "passive"))
      (node (ref "C21") (pin "1") (pinfunction "1_1") (pintype "passive"))
      (node (ref "C26") (pin "2") (pinfunction "2_2") (pintype "passive"))
      (node (ref "FB7") (pin "2") (pinfunction "2_2") (pintype "passive"))
      (node (ref "IC27") (pin "16") (pinfunction "VCCI_16") (pintype "power_in"))
      (node (ref "IC27") (pin "5") (pinfunction "VCCI_5") (pintype "power_in"))
      (node (ref "R17") (pin "2") (pinfunction "2_2") (pintype "passive"))
    )
    (net (code "17") (name "Net-(C139-Pad2)") (class "Default")
      (node (ref "C139") (pin "2") (pinfunction "2_2") (pintype "passive"))
      (node (ref "C22") (pin "1") (pinfunction "1_1") (pintype "passive"))
      (node (ref "C23") (pin "1") (pinfunction "1_1") (pintype "passive"))
      (node (ref "FB6") (pin "2") (pinfunction "2_2") (pintype "passive"))
      (node (ref "IC27") (pin "12") (pinfunction "VCCO_12") (pintype "power_in"))
      (node (ref "IC27") (pin "9") (pinfunction "VCCO_9") (pintype "power_in"))
    )
    (net (code "18") (name "Net-(D1-PadA)") (class "Default")
      (node (ref "D1") (pin "A") (pinfunction "A_A") (pintype "passive"))
      (node (ref "J2") (pin "1") (pinfunction "1_1") (pintype "bidirectional"))
    )
    (net (code "19") (name "Net-(D3-C)") (class "Default")
      (node (ref "C10") (pin "1") (pinfunction "1_1") (pintype "passive"))
      (node (ref "D3") (pin "1") (pinfunction "C_1") (pintype "passive"))
      (node (ref "FB5") (pin "2") (pinfunction "2_2") (pintype "passive"))
    )
    (net (code "20") (name "Net-(FB2-Pad2)") (class "Default")
      (node (ref "FB2") (pin "2") (pinfunction "2_2") (pintype "passive"))
      (node (ref "R6") (pin "1") (pinfunction "1_1") (pintype "passive"))
      (node (ref "R7") (pin "1") (pinfunction "1_1") (pintype "passive"))
    )
    (net (code "21") (name "Net-(FB3-Pad2)") (class "Default")
      (node (ref "FB3") (pin "2") (pinfunction "2_2") (pintype "passive"))
      (node (ref "R20") (pin "1") (pinfunction "1_1") (pintype "passive"))
      (node (ref "R8") (pin "1") (pinfunction "1_1") (pintype "passive"))
    )
    (net (code "22") (name "Net-(FB4-Pad2)") (class "Default")
      (node (ref "FB4") (pin "2") (pinfunction "2_2") (pintype "passive"))
      (node (ref "R19") (pin "1") (pinfunction "1_1") (pintype "passive"))
      (node (ref "R21") (pin "1") (pinfunction "1_1") (pintype "passive"))
    )
    (net (code "23") (name "Net-(IC1-GND)") (class "Default")
      (node (ref "FB5") (pin "1") (pinfunction "1_1") (pintype "passive"))
      (node (ref "IC1") (pin "2") (pinfunction "GND_2") (pintype "power_in"))
      (node (ref "R9") (pin "1") (pinfunction "1_1") (pintype "passive"))
    )
    (net (code "24") (name "Net-(IC1-IN)") (class "Default")
      (node (ref "FB1") (pin "2") (pinfunction "2_2") (pintype "passive"))
      (node (ref "IC1") (pin "3") (pinfunction "IN_3") (pintype "input"))
    )
    (net (code "25") (name "Net-(IC1-OUT)") (class "Default")
      (node (ref "IC1") (pin "1") (pinfunction "OUT_1") (pintype "power_in"))
      (node (ref "R4") (pin "1") (pinfunction "1_1") (pintype "passive"))
    )
    (net (code "26") (name "Net-(IC2-RF_IN)") (class "Default")
      (node (ref "C10") (pin "2") (pinfunction "2_2") (pintype "passive"))
      (node (ref "IC2") (pin "1") (pinfunction "RF_IN_1") (pintype "input"))
    )
    (net (code "27") (name "Net-(IC2-RF_OUT)") (class "Default")
      (node (ref "C12") (pin "2") (pinfunction "2_2") (pintype "passive"))
      (node (ref "FB3") (pin "1") (pinfunction "1_1") (pintype "passive"))
      (node (ref "IC2") (pin "3") (pinfunction "RF_OUT_3") (pintype "output"))
    )
    (net (code "28") (name "Net-(IC3-RF_IN)") (class "Default")
      (node (ref "C12") (pin "1") (pinfunction "1_1") (pintype "passive"))
      (node (ref "IC3") (pin "1") (pinfunction "RF_IN_1") (pintype "input"))
    )
    (net (code "29") (name "Net-(IC3-RF_OUT)") (class "Default")
      (node (ref "C14") (pin "1") (pinfunction "1_1") (pintype "passive"))
      (node (ref "C9") (pin "1") (pinfunction "1_1") (pintype "passive"))
      (node (ref "FB2") (pin "1") (pinfunction "1_1") (pintype "passive"))
      (node (ref "IC3") (pin "3") (pinfunction "RF_OUT_3") (pintype "output"))
      (node (ref "R11") (pin "1") (pinfunction "1_1") (pintype "passive"))
    )
    (net (code "30") (name "Net-(IC4-RF_IN)") (class "Default")
      (node (ref "C11") (pin "2") (pinfunction "2_2") (pintype "passive"))
      (node (ref "C9") (pin "2") (pinfunction "2_2") (pintype "passive"))
      (node (ref "IC4") (pin "1") (pinfunction "RF_IN_1") (pintype "input"))
    )
    (net (code "31") (name "Net-(IC4-RF_OUT)") (class "Default")
      (node (ref "C13") (pin "1") (pinfunction "1_1") (pintype "passive"))
      (node (ref "C15") (pin "2") (pinfunction "2_2") (pintype "passive"))
      (node (ref "FB4") (pin "1") (pinfunction "1_1") (pintype "passive"))
      (node (ref "IC4") (pin "3") (pinfunction "RF_OUT_3") (pintype "output"))
    )
    (net (code "32") (name "Net-(IC5-COMP)") (class "Default")
      (node (ref "IC5") (pin "5") (pinfunction "COMP_5") (pintype "input"))
      (node (ref "R10") (pin "2") (pinfunction "2_2") (pintype "passive"))
      (node (ref "R5") (pin "1") (pinfunction "1_1") (pintype "passive"))
    )
    (net (code "33") (name "Net-(IC5-DRVC)") (class "Default")
      (node (ref "IC5") (pin "8") (pinfunction "DRVC_8") (pintype "input"))
      (node (ref "R12") (pin "2") (pinfunction "2_2") (pintype "passive"))
    )
    (net (code "34") (name "Net-(IC5-Ipk)") (class "Default")
      (node (ref "IC5") (pin "7") (pinfunction "Ipk_7") (pintype "input"))
      (node (ref "L2") (pin "1") (pintype "passive"))
      (node (ref "R12") (pin "1") (pinfunction "1_1") (pintype "passive"))
      (node (ref "R13") (pin "2") (pinfunction "2_2") (pintype "passive"))
      (node (ref "R15") (pin "2") (pinfunction "2_2") (pintype "passive"))
    )
    (net (code "35") (name "Net-(IC5-SWC)") (class "Default")
      (node (ref "D2") (pin "A") (pinfunction "A_A") (pintype "passive"))
      (node (ref "IC5") (pin "1") (pinfunction "SWC_1") (pintype "bidirectional"))
      (node (ref "L2") (pin "2") (pintype "passive"))
    )
    (net (code "36") (name "Net-(IC5-TC)") (class "Default")
      (node (ref "C16") (pin "1") (pinfunction "1_1") (pintype "passive"))
      (node (ref "IC5") (pin "3") (pinfunction "TC_3") (pintype "passive"))
    )
    (net (code "37") (name "Net-(IC6-IN)") (class "Default")
      (node (ref "C138") (pin "2") (pinfunction "2_2") (pintype "passive"))
      (node (ref "IC6") (pin "3") (pinfunction "IN_3") (pintype "input"))
      (node (ref "R22") (pin "2") (pinfunction "2_2") (pintype "passive"))
      (node (ref "R23") (pin "2") (pinfunction "2_2") (pintype "passive"))
    )
    (net (code "38") (name "Net-(IC27-HYS)") (class "Default")
      (node (ref "IC27") (pin "14") (pinfunction "HYS_14") (pintype "input"))
      (node (ref "R16") (pin "2") (pinfunction "2_2") (pintype "passive"))
    )
    (net (code "39") (name "Net-(IC27-LE)") (class "Default")
      (node (ref "IC27") (pin "7") (pinfunction "LE_7") (pintype "input"))
      (node (ref "R17") (pin "1") (pinfunction "1_1") (pintype "passive"))
    )
    (net (code "40") (name "Net-(IC27-Q)") (class "Default")
      (node (ref "C24") (pin "1") (pinfunction "1_1") (pintype "passive"))
      (node (ref "IC27") (pin "11") (pinfunction "Q_11") (pintype "output"))
    )
    (net (code "41") (name "Net-(IC27-VTN)") (class "Default")
      (node (ref "C25") (pin "1") (pinfunction "1_1") (pintype "passive"))
      (node (ref "IC27") (pin "1") (pinfunction "VTP_1") (pintype "input"))
      (node (ref "IC27") (pin "4") (pinfunction "VTN_4") (pintype "input"))
    )
    (net (code "42") (name "Net-(IC27-~{LE})") (class "Default")
      (node (ref "IC27") (pin "6") (pinfunction "~{LE}_6") (pintype "input"))
      (node (ref "R18") (pin "1") (pinfunction "1_1") (pintype "passive"))
    )
    (net (code "43") (name "Net-(IC27-~{Q})") (class "Default")
      (node (ref "C127") (pin "2") (pinfunction "2_2") (pintype "passive"))
      (node (ref "IC27") (pin "10") (pinfunction "~{Q}_10") (pintype "output"))
    )
    (net (code "44") (name "Net-(J3-Pad1)") (class "Default")
      (node (ref "J3") (pin "1") (pinfunction "1_1") (pintype "bidirectional"))
      (node (ref "R14") (pin "2") (pinfunction "2_2") (pintype "passive"))
    )
    (net (code "45") (name "Net-(R4-Pad2)") (class "Default")
      (node (ref "R4") (pin "2") (pinfunction "2_2") (pintype "passive"))
      (node (ref "R4") (pin "3") (pinfunction "3_3") (pintype "passive"))
      (node (ref "R9") (pin "2") (pinfunction "2_2") (pintype "passive"))
    )
    (net (code "46") (name "Net-(TR1-P)") (class "Default")
      (node (ref "C19") (pin "1") (pinfunction "1_1") (pintype "passive"))
      (node (ref "TR1") (pin "4") (pinfunction "P_4") (pintype "passive"))
    )
    (net (code "47") (name "Net-(TR1-PDOT)") (class "Default")
      (node (ref "C13") (pin "2") (pinfunction "2_2") (pintype "passive"))
      (node (ref "TR1") (pin "6") (pinfunction "PDOT_6") (pintype "passive"))
    )
    (net (code "48") (name "P5V0") (class "Default")
      (node (ref "C129") (pin "1") (pinfunction "1_1") (pintype "passive"))
      (node (ref "FB6") (pin "1") (pinfunction "1_1") (pintype "passive"))
      (node (ref "FB7") (pin "1") (pinfunction "1_1") (pintype "passive"))
      (node (ref "IC6") (pin "1") (pinfunction "OUT_1") (pintype "power_in"))
    )
    (net (code "49") (name "P12V0") (class "Default")
      (node (ref "C137") (pin "2") (pinfunction "2_2") (pintype "passive"))
      (node (ref "C17") (pin "2") (pinfunction "2_2") (pintype "passive"))
      (node (ref "C18") (pin "1") (pinfunction "1_1") (pintype "passive"))
      (node (ref "D1") (pin "K") (pinfunction "K_K") (pintype "passive"))
      (node (ref "IC5") (pin "6") (pinfunction "VCC_6") (pintype "power_in"))
      (node (ref "R1") (pin "2") (pinfunction "2_2") (pintype "passive"))
      (node (ref "R13") (pin "1") (pinfunction "1_1") (pintype "passive"))
      (node (ref "R15") (pin "1") (pinfunction "1_1") (pintype "passive"))
      (node (ref "R2") (pin "2") (pinfunction "2_2") (pintype "passive"))
      (node (ref "R22") (pin "1") (pinfunction "1_1") (pintype "passive"))
      (node (ref "R23") (pin "1") (pinfunction "1_1") (pintype "passive"))
      (node (ref "R3") (pin "2") (pinfunction "2_2") (pintype "passive"))
    )
    (net (code "50") (name "P34V0") (class "Default")
      (node (ref "C6") (pin "1") (pinfunction "1_1") (pintype "passive"))
      (node (ref "C7") (pin "1") (pinfunction "1_1") (pintype "passive"))
      (node (ref "C8") (pin "2") (pinfunction "2_2") (pintype "passive"))
      (node (ref "FB1") (pin "1") (pinfunction "1_1") (pintype "passive"))
      (node (ref "L1") (pin "2") (pintype "passive"))
    )
    (net (code "51") (name "unconnected-(IC27-VCCO{slash}VTT-Pad8)") (class "Default")
      (node (ref "IC27") (pin "8") (pinfunction "VCCO/VTT_8") (pintype "power_in+no_connect"))
    )
    (net (code "52") (name "unconnected-(J2-Pad2)") (class "Default")
      (node (ref "J2") (pin "2") (pinfunction "2_2") (pintype "bidirectional"))
    )
    (net (code "53") (name "unconnected-(TR1-NC-Pad2)") (class "Default")
      (node (ref "TR1") (pin "2") (pinfunction "NC_2") (pintype "passive"))
    )
  )
)
